# d1-relay-module-shield.net
KiCad netlist of a schematic drawn in EAGLE
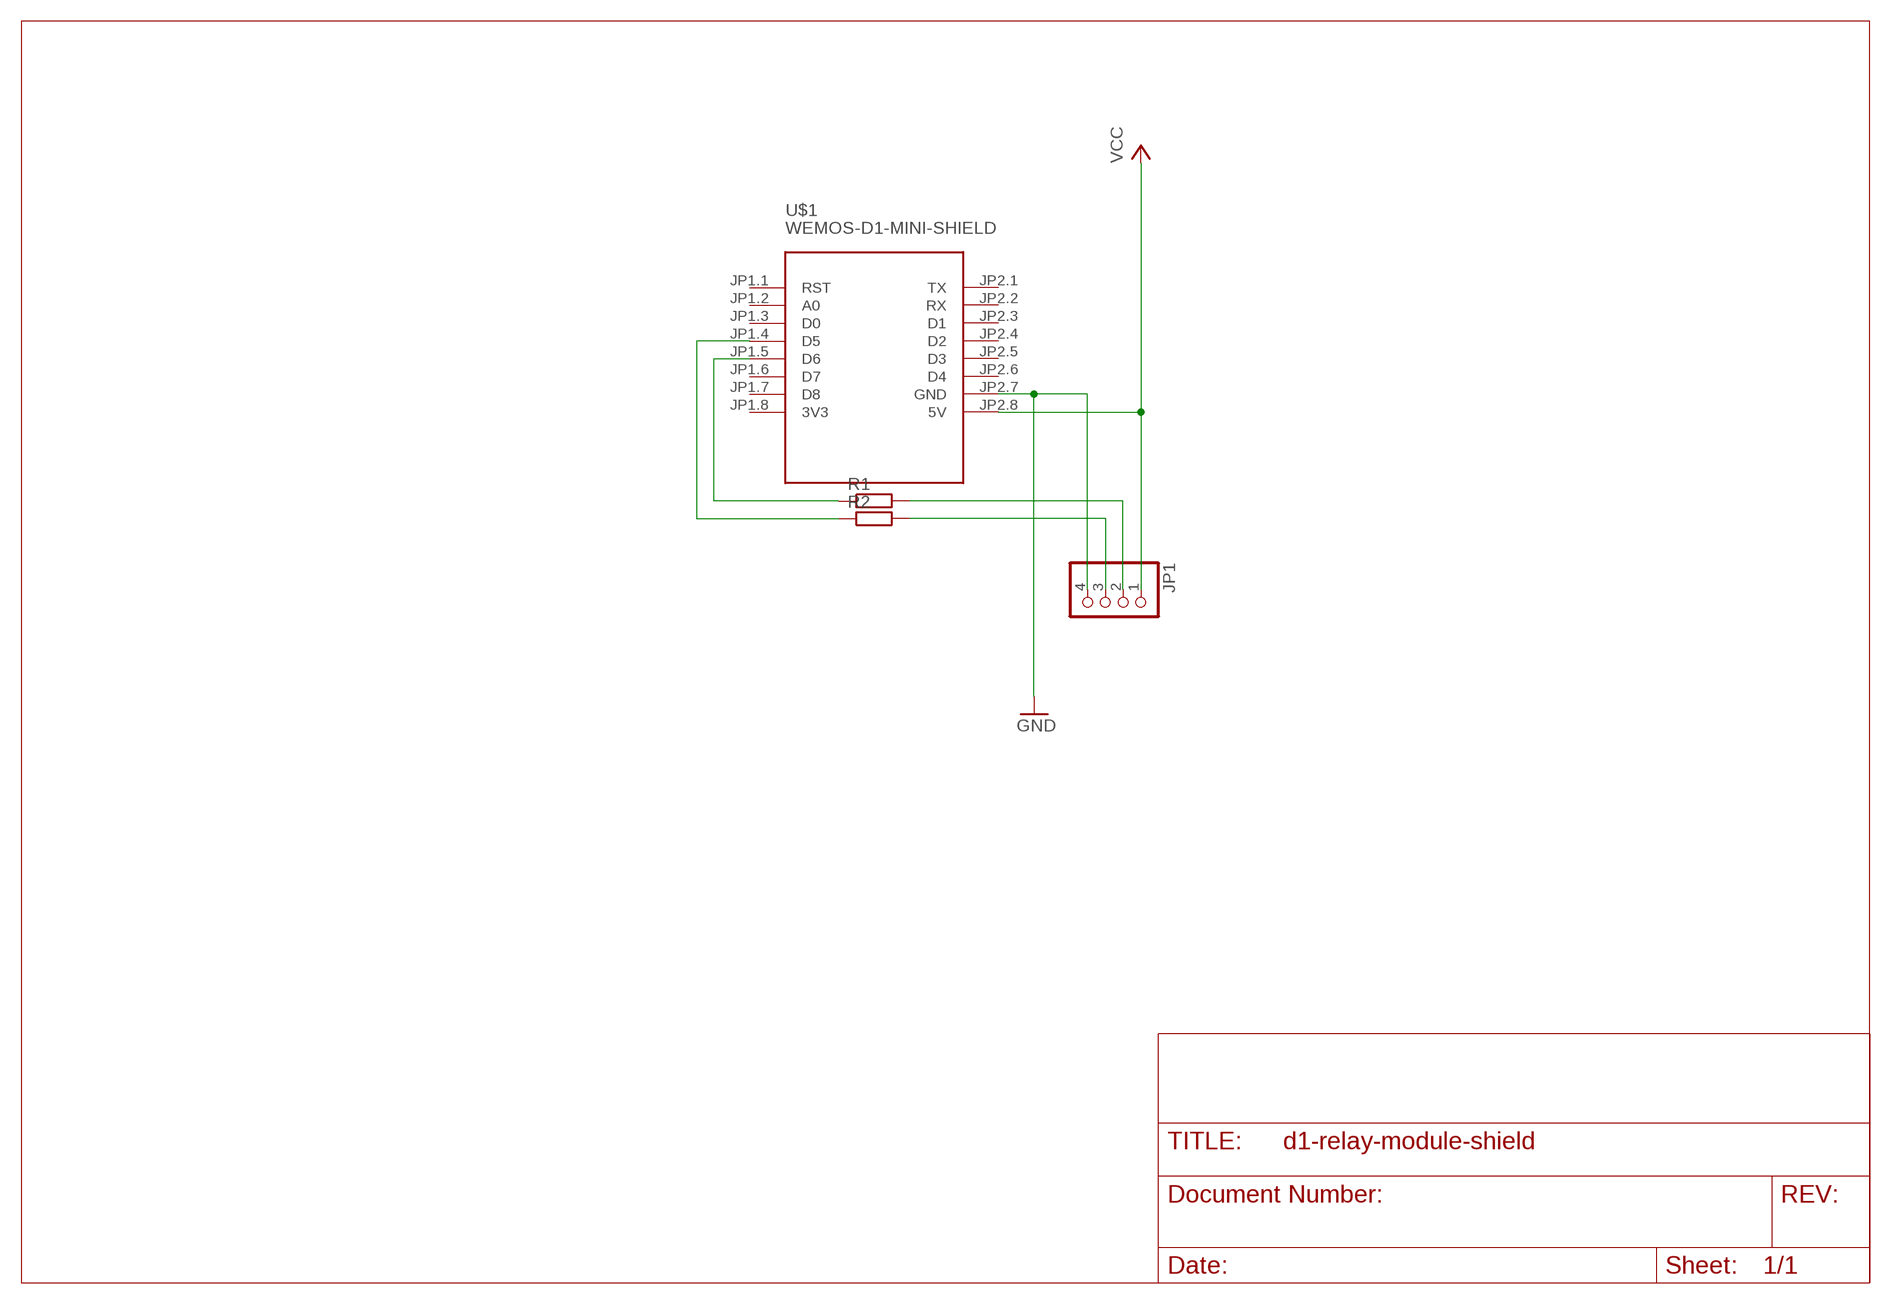
[diagram p0: schematic, sheet 1]

(export (version "E")
  (design (tool "Eeschema 10.0.6"))
  (components
    (comp (ref "JP1")
      (value "PINHD-1X4")
      (footprint "eagle-import:1X04")
      (libsource (lib "eagle-import") (part "PINHD-1X4"))
    )
    (comp (ref "R1")
      (value "R-EU_R0603")
      (footprint "eagle-import:R0603")
      (libsource (lib "eagle-import") (part "R-EU_R0603"))
    )
    (comp (ref "R2")
      (value "R-EU_R0603")
      (footprint "eagle-import:R0603")
      (libsource (lib "eagle-import") (part "R-EU_R0603"))
    )
    (comp (ref "U$1")
      (value "WEMOS-D1-MINI-SHIELD")
      (footprint "eagle-import:WEMOS-D1-MINI-SHIELD")
      (libsource (lib "eagle-import") (part "WEMOS-D1-MINI-SHIELD"))
    )
  )
  (nets
    (net (code "1") (name "/3V3") (class "Default")
      (node (ref "U$1") (pin "JP1.8") (pinfunction "3V3_JP1.8") (pintype "power_in"))
    )
    (net (code "2") (name "GND") (class "Default")
      (node (ref "JP1") (pin "4") (pinfunction "4_4") (pintype "passive"))
      (node (ref "U$1") (pin "JP2.7") (pinfunction "GND_JP2.7") (pintype "power_in"))
    )
    (net (code "3") (name "Net-(JP1-Pad2)") (class "Default")
      (node (ref "JP1") (pin "2") (pinfunction "2_2") (pintype "passive"))
      (node (ref "R1") (pin "2") (pinfunction "2_2") (pintype "passive"))
    )
    (net (code "4") (name "Net-(JP1-Pad3)") (class "Default")
      (node (ref "JP1") (pin "3") (pinfunction "3_3") (pintype "passive"))
      (node (ref "R2") (pin "2") (pinfunction "2_2") (pintype "passive"))
    )
    (net (code "5") (name "Net-(U$1-D5)") (class "Default")
      (node (ref "R2") (pin "1") (pinfunction "1_1") (pintype "passive"))
      (node (ref "U$1") (pin "JP1.4") (pinfunction "D5_JP1.4") (pintype "bidirectional"))
    )
    (net (code "6") (name "Net-(U$1-D6)") (class "Default")
      (node (ref "R1") (pin "1") (pinfunction "1_1") (pintype "passive"))
      (node (ref "U$1") (pin "JP1.5") (pinfunction "D6_JP1.5") (pintype "bidirectional"))
    )
    (net (code "7") (name "VCC") (class "Default")
      (node (ref "JP1") (pin "1") (pinfunction "1_1") (pintype "passive"))
      (node (ref "U$1") (pin "JP2.8") (pinfunction "5V_JP2.8") (pintype "power_in"))
    )
    (net (code "8") (name "unconnected-(U$1-A0-PadJP1.2)") (class "Default")
      (node (ref "U$1") (pin "JP1.2") (pinfunction "A0_JP1.2") (pintype "bidirectional"))
    )
    (net (code "9") (name "unconnected-(U$1-D0-PadJP1.3)") (class "Default")
      (node (ref "U$1") (pin "JP1.3") (pinfunction "D0_JP1.3") (pintype "bidirectional"))
    )
    (net (code "10") (name "unconnected-(U$1-D1-PadJP2.3)") (class "Default")
      (node (ref "U$1") (pin "JP2.3") (pinfunction "D1_JP2.3") (pintype "bidirectional"))
    )
    (net (code "11") (name "unconnected-(U$1-D2-PadJP2.4)") (class "Default")
      (node (ref "U$1") (pin "JP2.4") (pinfunction "D2_JP2.4") (pintype "bidirectional"))
    )
    (net (code "12") (name "unconnected-(U$1-D3-PadJP2.5)") (class "Default")
      (node (ref "U$1") (pin "JP2.5") (pinfunction "D3_JP2.5") (pintype "bidirectional"))
    )
    (net (code "13") (name "unconnected-(U$1-D4-PadJP2.6)") (class "Default")
      (node (ref "U$1") (pin "JP2.6") (pinfunction "D4_JP2.6") (pintype "bidirectional"))
    )
    (net (code "14") (name "unconnected-(U$1-D7-PadJP1.6)") (class "Default")
      (node (ref "U$1") (pin "JP1.6") (pinfunction "D7_JP1.6") (pintype "bidirectional"))
    )
    (net (code "15") (name "unconnected-(U$1-D8-PadJP1.7)") (class "Default")
      (node (ref "U$1") (pin "JP1.7") (pinfunction "D8_JP1.7") (pintype "bidirectional"))
    )
    (net (code "16") (name "unconnected-(U$1-RST-PadJP1.1)") (class "Default")
      (node (ref "U$1") (pin "JP1.1") (pinfunction "RST_JP1.1") (pintype "bidirectional"))
    )
    (net (code "17") (name "unconnected-(U$1-RX-PadJP2.2)") (class "Default")
      (node (ref "U$1") (pin "JP2.2") (pinfunction "RX_JP2.2") (pintype "bidirectional"))
    )
    (net (code "18") (name "unconnected-(U$1-TX-PadJP2.1)") (class "Default")
      (node (ref "U$1") (pin "JP2.1") (pinfunction "TX_JP2.1") (pintype "bidirectional"))
    )
  )
)
